# BeeCee.net
KiCad netlist of a schematic drawn in EAGLE
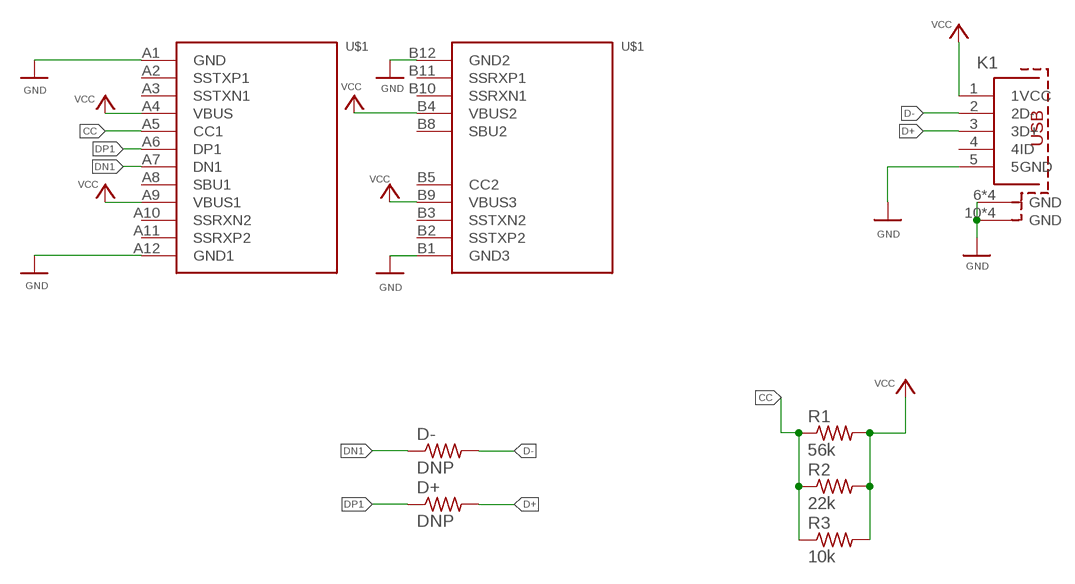
[diagram p0: schematic, sheet 1]

(export (version "E")
  (design (tool "Eeschema 10.0.6"))
  (components
    (comp (ref "D+")
      (value "DNP")
      (footprint "eagle-import:R0805")
      (libsource (lib "eagle-import") (part "R-US_R0805"))
    )
    (comp (ref "D-")
      (value "DNP")
      (footprint "eagle-import:R0805")
      (libsource (lib "eagle-import") (part "R-US_R0805"))
    )
    (comp (ref "K1")
      (value "629105150921")
      (footprint "eagle-import:629105150921")
      (libsource (lib "eagle-import") (part "629105150921"))
    )
    (comp (ref "R1")
      (value "56k")
      (footprint "eagle-import:R0805")
      (libsource (lib "eagle-import") (part "R-US_R0805"))
    )
    (comp (ref "R2")
      (value "22k")
      (footprint "eagle-import:R0805")
      (libsource (lib "eagle-import") (part "R-US_R0805"))
    )
    (comp (ref "R3")
      (value "10k")
      (footprint "eagle-import:R0805")
      (libsource (lib "eagle-import") (part "R-US_R0805"))
    )
    (comp (ref "U$1")
      (value "632712000011(T)")
      (footprint "eagle-import:632712000011")
      (libsource (lib "eagle-import") (part "632712000011(T)"))
    )
  )
  (nets
    (net (code "1") (name "CC") (class "Default")
      (node (ref "R1") (pin "1") (pinfunction "1_1") (pintype "passive"))
      (node (ref "R2") (pin "1") (pinfunction "1_1") (pintype "passive"))
      (node (ref "R3") (pin "1") (pinfunction "1_1") (pintype "passive"))
      (node (ref "U$1") (pin "A5") (pinfunction "CC1_A5") (pintype "bidirectional"))
    )
    (net (code "2") (name "D+") (class "Default")
      (node (ref "D+") (pin "2") (pinfunction "2_2") (pintype "passive"))
      (node (ref "K1") (pin "3") (pinfunction "3D+_3") (pintype "passive"))
    )
    (net (code "3") (name "D-") (class "Default")
      (node (ref "D-") (pin "2") (pinfunction "2_2") (pintype "passive"))
      (node (ref "K1") (pin "2") (pinfunction "2D-_2") (pintype "passive"))
    )
    (net (code "4") (name "DN1") (class "Default")
      (node (ref "D-") (pin "1") (pinfunction "1_1") (pintype "passive"))
      (node (ref "U$1") (pin "A7") (pinfunction "DN1_A7") (pintype "bidirectional"))
    )
    (net (code "5") (name "DP1") (class "Default")
      (node (ref "D+") (pin "1") (pinfunction "1_1") (pintype "passive"))
      (node (ref "U$1") (pin "A6") (pinfunction "DP1_A6") (pintype "bidirectional"))
    )
    (net (code "6") (name "GND") (class "Default")
      (node (ref "K1") (pin "10") (pinfunction "GND_10") (pintype "bidirectional"))
      (node (ref "K1") (pin "11") (pinfunction "GND_11") (pintype "bidirectional"))
      (node (ref "K1") (pin "12") (pinfunction "GND_12") (pintype "bidirectional"))
      (node (ref "K1") (pin "13") (pinfunction "GND_13") (pintype "bidirectional"))
      (node (ref "K1") (pin "5") (pinfunction "5GND_5") (pintype "passive"))
      (node (ref "K1") (pin "6") (pinfunction "GND_6") (pintype "bidirectional"))
      (node (ref "K1") (pin "7") (pinfunction "GND_7") (pintype "bidirectional"))
      (node (ref "K1") (pin "8") (pinfunction "GND_8") (pintype "bidirectional"))
      (node (ref "K1") (pin "9") (pinfunction "GND_9") (pintype "bidirectional"))
      (node (ref "U$1") (pin "A1") (pinfunction "GND_A1") (pintype "bidirectional"))
      (node (ref "U$1") (pin "A12") (pinfunction "GND1_A12") (pintype "bidirectional"))
      (node (ref "U$1") (pin "B1") (pinfunction "GND3_B1") (pintype "bidirectional"))
      (node (ref "U$1") (pin "B12") (pinfunction "GND2_B12") (pintype "bidirectional"))
    )
    (net (code "7") (name "VCC") (class "Default")
      (node (ref "K1") (pin "1") (pinfunction "1VCC_1") (pintype "passive"))
      (node (ref "R1") (pin "2") (pinfunction "2_2") (pintype "passive"))
      (node (ref "R2") (pin "2") (pinfunction "2_2") (pintype "passive"))
      (node (ref "R3") (pin "2") (pinfunction "2_2") (pintype "passive"))
      (node (ref "U$1") (pin "A4") (pinfunction "VBUS_A4") (pintype "bidirectional"))
      (node (ref "U$1") (pin "A9") (pinfunction "VBUS1_A9") (pintype "bidirectional"))
      (node (ref "U$1") (pin "B4") (pinfunction "VBUS2_B4") (pintype "bidirectional"))
      (node (ref "U$1") (pin "B9") (pinfunction "VBUS3_B9") (pintype "bidirectional"))
    )
    (net (code "8") (name "unconnected-(K1-4ID-Pad4)") (class "Default")
      (node (ref "K1") (pin "4") (pinfunction "4ID_4") (pintype "passive"))
    )
    (net (code "9") (name "unconnected-(U$1-CC2-PadB5)") (class "Default")
      (node (ref "U$1") (pin "B5") (pinfunction "CC2_B5") (pintype "bidirectional"))
    )
    (net (code "10") (name "unconnected-(U$1-SBU1-PadA8)") (class "Default")
      (node (ref "U$1") (pin "A8") (pinfunction "SBU1_A8") (pintype "bidirectional"))
    )
    (net (code "11") (name "unconnected-(U$1-SBU2-PadB8)") (class "Default")
      (node (ref "U$1") (pin "B8") (pinfunction "SBU2_B8") (pintype "bidirectional"))
    )
    (net (code "12") (name "unconnected-(U$1-SSRXN1-PadB10)") (class "Default")
      (node (ref "U$1") (pin "B10") (pinfunction "SSRXN1_B10") (pintype "bidirectional"))
    )
    (net (code "13") (name "unconnected-(U$1-SSRXN2-PadA10)") (class "Default")
      (node (ref "U$1") (pin "A10") (pinfunction "SSRXN2_A10") (pintype "bidirectional"))
    )
    (net (code "14") (name "unconnected-(U$1-SSRXP1-PadB11)") (class "Default")
      (node (ref "U$1") (pin "B11") (pinfunction "SSRXP1_B11") (pintype "bidirectional"))
    )
    (net (code "15") (name "unconnected-(U$1-SSRXP2-PadA11)") (class "Default")
      (node (ref "U$1") (pin "A11") (pinfunction "SSRXP2_A11") (pintype "bidirectional"))
    )
    (net (code "16") (name "unconnected-(U$1-SSTXN1-PadA3)") (class "Default")
      (node (ref "U$1") (pin "A3") (pinfunction "SSTXN1_A3") (pintype "bidirectional"))
    )
    (net (code "17") (name "unconnected-(U$1-SSTXN2-PadB3)") (class "Default")
      (node (ref "U$1") (pin "B3") (pinfunction "SSTXN2_B3") (pintype "bidirectional"))
    )
    (net (code "18") (name "unconnected-(U$1-SSTXP1-PadA2)") (class "Default")
      (node (ref "U$1") (pin "A2") (pinfunction "SSTXP1_A2") (pintype "bidirectional"))
    )
    (net (code "19") (name "unconnected-(U$1-SSTXP2-PadB2)") (class "Default")
      (node (ref "U$1") (pin "B2") (pinfunction "SSTXP2_B2") (pintype "bidirectional"))
    )
  )
)
